# M2.net
KiCad netlist of a schematic drawn in Altium Designer
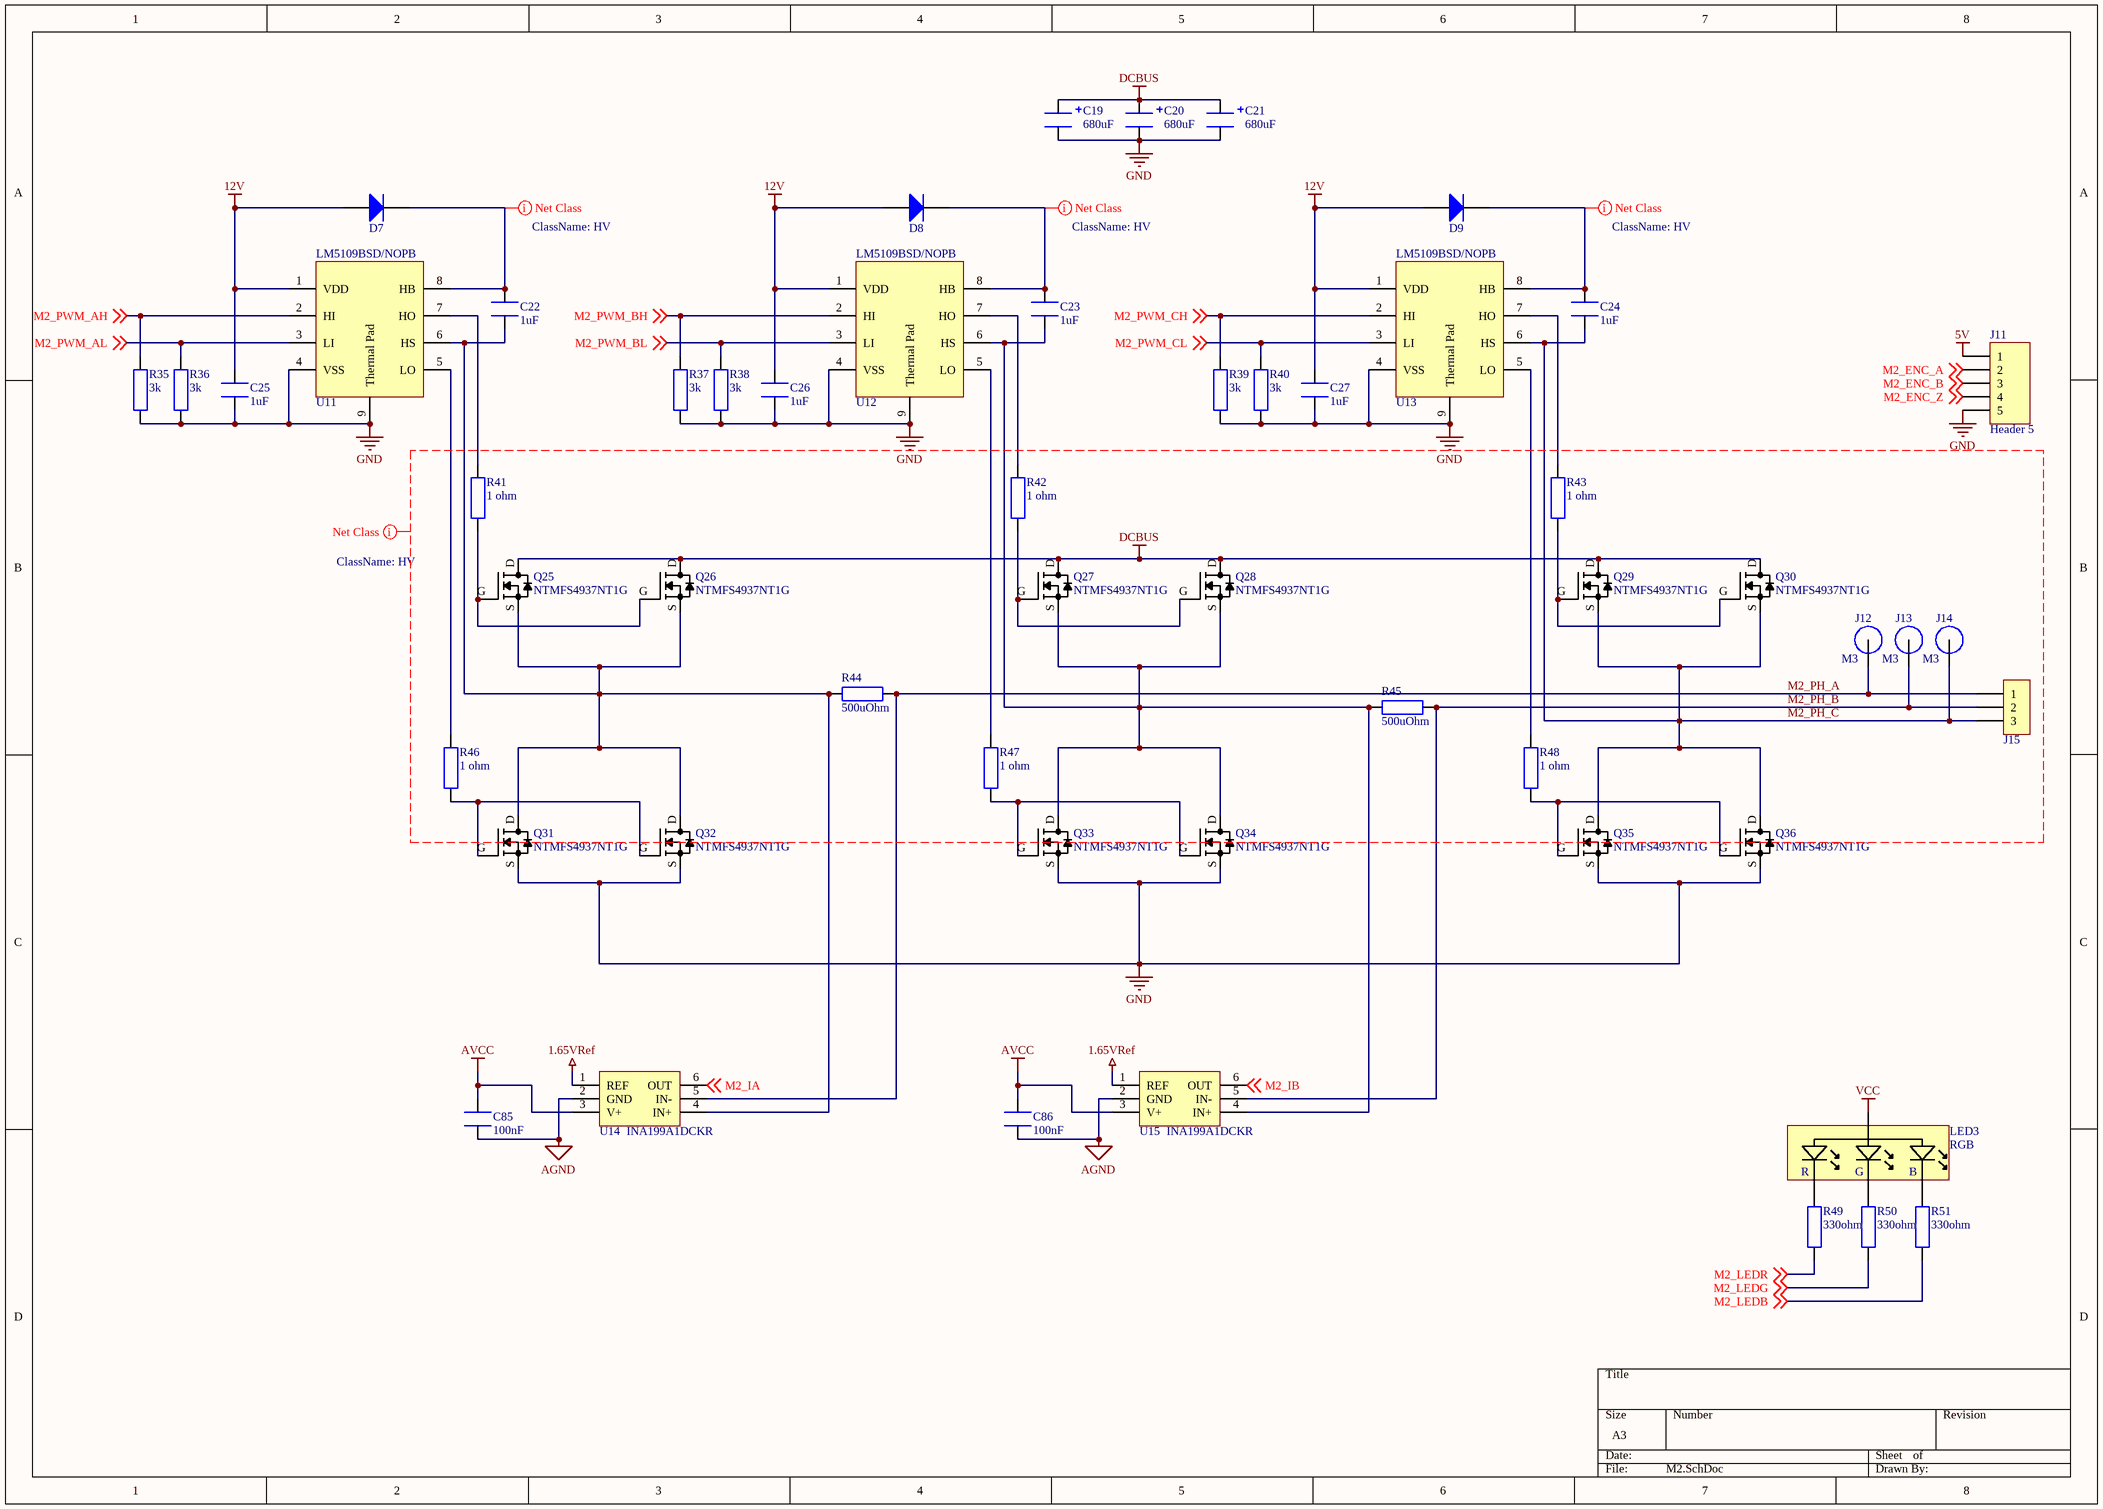
[diagram p0: M2.SchDoc]

(export (version "E")
  (design (tool "Eeschema 10.0.6"))
  (components
    (comp (ref "C19")
      (value "680uF")
      (footprint "CAPE10.0MM_Rad_10x14mm")
      (description "CAP, ALU ELEC, 680UF, 35V, RAD")
      (fields (field (name "Comment") "35ZLH680MEFC10X23"))
      (libsource (lib "CustomComponents") (part "35ZLH680MEFC10X23"))
    )
    (comp (ref "C20")
      (value "680uF")
      (footprint "CAPE10.0MM_Rad_10x14mm")
      (description "CAP, ALU ELEC, 680UF, 35V, RAD")
      (fields (field (name "Comment") "35ZLH680MEFC10X23"))
      (libsource (lib "CustomComponents") (part "35ZLH680MEFC10X23"))
    )
    (comp (ref "C21")
      (value "680uF")
      (footprint "CAPE10.0MM_Rad_10x14mm")
      (description "CAP, ALU ELEC, 680UF, 35V, RAD")
      (fields (field (name "Comment") "35ZLH680MEFC10X23"))
      (libsource (lib "CustomComponents") (part "35ZLH680MEFC10X23"))
    )
    (comp (ref "C22")
      (value "1uF")
      (footprint "1608[0603]")
      (description "CAP, MLCC, X5R, 1UF, 16V, 0603")
      (fields (field (name "Comment") "MC0603X105K160"))
      (libsource (lib "CustomComponents") (part "MC0603X105K160"))
    )
    (comp (ref "C23")
      (value "1uF")
      (footprint "1608[0603]")
      (description "CAP, MLCC, X5R, 1UF, 16V, 0603")
      (fields (field (name "Comment") "MC0603X105K160"))
      (libsource (lib "CustomComponents") (part "MC0603X105K160"))
    )
    (comp (ref "C24")
      (value "1uF")
      (footprint "1608[0603]")
      (description "CAP, MLCC, X5R, 1UF, 16V, 0603")
      (fields (field (name "Comment") "MC0603X105K160"))
      (libsource (lib "CustomComponents") (part "MC0603X105K160"))
    )
    (comp (ref "C25")
      (value "1uF")
      (footprint "1608[0603]")
      (description "CAP, MLCC, X5R, 1UF, 16V, 0603")
      (fields (field (name "Comment") "MC0603X105K160"))
      (libsource (lib "CustomComponents") (part "MC0603X105K160"))
    )
    (comp (ref "C26")
      (value "1uF")
      (footprint "1608[0603]")
      (description "CAP, MLCC, X5R, 1UF, 16V, 0603")
      (fields (field (name "Comment") "MC0603X105K160"))
      (libsource (lib "CustomComponents") (part "MC0603X105K160"))
    )
    (comp (ref "C27")
      (value "1uF")
      (footprint "1608[0603]")
      (description "CAP, MLCC, X5R, 1UF, 16V, 0603")
      (fields (field (name "Comment") "MC0603X105K160"))
      (libsource (lib "CustomComponents") (part "MC0603X105K160"))
    )
    (comp (ref "C85")
      (value "100nF")
      (footprint "1608[0603]")
      (description "CAP, MLCC, X7R, 100NF, 16V, 0603")
      (fields (field (name "Comment") "MC0603B104K160CT"))
      (libsource (lib "CustomComponents") (part "MC0603B104K160CT"))
    )
    (comp (ref "C86")
      (value "100nF")
      (footprint "1608[0603]")
      (description "CAP, MLCC, X7R, 100NF, 16V, 0603")
      (fields (field (name "Comment") "MC0603B104K160CT"))
      (libsource (lib "CustomComponents") (part "MC0603B104K160CT"))
    )
    (comp (ref "D7")
      (value "RB521S30T1G")
      (footprint "SOD523F")
      (description "DIODE, SCHOTTKY, 200MA, 30V")
      (libsource (lib "CustomComponents") (part "RB521S30T1G"))
    )
    (comp (ref "D8")
      (value "RB521S30T1G")
      (footprint "SOD523F")
      (description "DIODE, SCHOTTKY, 200MA, 30V")
      (libsource (lib "CustomComponents") (part "RB521S30T1G"))
    )
    (comp (ref "D9")
      (value "RB521S30T1G")
      (footprint "SOD523F")
      (description "DIODE, SCHOTTKY, 200MA, 30V")
      (libsource (lib "CustomComponents") (part "RB521S30T1G"))
    )
    (comp (ref "J11")
      (value "Header 5")
      (footprint "HDR1X5")
      (description "Header, 5-Pin")
      (fields (field (name "PUBLISHER") "Altium Limited"))
      (libsource (lib "Miscellaneous Connectors") (part "Header 5"))
    )
    (comp (ref "J12")
      (value "M3")
      (footprint "M3 Spade Hole")
      (description "M3 Spade Terminal")
      (libsource (lib "CustomComponents") (part "M3 Spade Terminal"))
    )
    (comp (ref "J13")
      (value "M3")
      (footprint "M3 Spade Hole")
      (description "M3 Spade Terminal")
      (libsource (lib "CustomComponents") (part "M3 Spade Terminal"))
    )
    (comp (ref "J14")
      (value "M3")
      (footprint "M3 Spade Hole")
      (description "M3 Spade Terminal")
      (libsource (lib "CustomComponents") (part "M3 Spade Terminal"))
    )
    (comp (ref "J15")
      (value "MC000051")
      (footprint "MC000051")
      (description "TERMINAL BLOCK, WIRE TO BRD, 3POS, 10AWG")
      (libsource (lib "CustomComponents") (part "MC000051"))
    )
    (comp (ref "LED3")
      (value "RGB")
      (footprint "ASMB-MTB1")
      (description "LED, HB, RGB, 0.09W, PLCC-4")
      (libsource (lib "CustomComponents") (part "ASMB-MTB1-0A3A2"))
    )
    (comp (ref "Q25")
      (value "NTMFS4937NT1G")
      (footprint "SO8FL")
      (description "MOSFET, N CH, 30V, 70A, SO-8 FL")
      (libsource (lib "CustomComponents") (part "NTMFS4937NT1G"))
    )
    (comp (ref "Q26")
      (value "NTMFS4937NT1G")
      (footprint "SO8FL")
      (description "MOSFET, N CH, 30V, 70A, SO-8 FL")
      (libsource (lib "CustomComponents") (part "NTMFS4937NT1G"))
    )
    (comp (ref "Q27")
      (value "NTMFS4937NT1G")
      (footprint "SO8FL")
      (description "MOSFET, N CH, 30V, 70A, SO-8 FL")
      (libsource (lib "CustomComponents") (part "NTMFS4937NT1G"))
    )
    (comp (ref "Q28")
      (value "NTMFS4937NT1G")
      (footprint "SO8FL")
      (description "MOSFET, N CH, 30V, 70A, SO-8 FL")
      (libsource (lib "CustomComponents") (part "NTMFS4937NT1G"))
    )
    (comp (ref "Q29")
      (value "NTMFS4937NT1G")
      (footprint "SO8FL")
      (description "MOSFET, N CH, 30V, 70A, SO-8 FL")
      (libsource (lib "CustomComponents") (part "NTMFS4937NT1G"))
    )
    (comp (ref "Q30")
      (value "NTMFS4937NT1G")
      (footprint "SO8FL")
      (description "MOSFET, N CH, 30V, 70A, SO-8 FL")
      (libsource (lib "CustomComponents") (part "NTMFS4937NT1G"))
    )
    (comp (ref "Q31")
      (value "NTMFS4937NT1G")
      (footprint "SO8FL")
      (description "MOSFET, N CH, 30V, 70A, SO-8 FL")
      (libsource (lib "CustomComponents") (part "NTMFS4937NT1G"))
    )
    (comp (ref "Q32")
      (value "NTMFS4937NT1G")
      (footprint "SO8FL")
      (description "MOSFET, N CH, 30V, 70A, SO-8 FL")
      (libsource (lib "CustomComponents") (part "NTMFS4937NT1G"))
    )
    (comp (ref "Q33")
      (value "NTMFS4937NT1G")
      (footprint "SO8FL")
      (description "MOSFET, N CH, 30V, 70A, SO-8 FL")
      (libsource (lib "CustomComponents") (part "NTMFS4937NT1G"))
    )
    (comp (ref "Q34")
      (value "NTMFS4937NT1G")
      (footprint "SO8FL")
      (description "MOSFET, N CH, 30V, 70A, SO-8 FL")
      (libsource (lib "CustomComponents") (part "NTMFS4937NT1G"))
    )
    (comp (ref "Q35")
      (value "NTMFS4937NT1G")
      (footprint "SO8FL")
      (description "MOSFET, N CH, 30V, 70A, SO-8 FL")
      (libsource (lib "CustomComponents") (part "NTMFS4937NT1G"))
    )
    (comp (ref "Q36")
      (value "NTMFS4937NT1G")
      (footprint "SO8FL")
      (description "MOSFET, N CH, 30V, 70A, SO-8 FL")
      (libsource (lib "CustomComponents") (part "NTMFS4937NT1G"))
    )
    (comp (ref "R35")
      (value "3k")
      (footprint "RESC1608X55N")
      (description "RESISTOR, 0603, 3K, 1%, ANTI SULFUR")
      (fields (field (name "Comment") "MCMR06X3001FTL"))
      (libsource (lib "CustomComponents") (part "MCMR06X3001FTL"))
    )
    (comp (ref "R36")
      (value "3k")
      (footprint "RESC1608X55N")
      (description "RESISTOR, 0603, 3K, 1%, ANTI SULFUR")
      (fields (field (name "Comment") "MCMR06X3001FTL"))
      (libsource (lib "CustomComponents") (part "MCMR06X3001FTL"))
    )
    (comp (ref "R37")
      (value "3k")
      (footprint "RESC1608X55N")
      (description "RESISTOR, 0603, 3K, 1%, ANTI SULFUR")
      (fields (field (name "Comment") "MCMR06X3001FTL"))
      (libsource (lib "CustomComponents") (part "MCMR06X3001FTL"))
    )
    (comp (ref "R38")
      (value "3k")
      (footprint "RESC1608X55N")
      (description "RESISTOR, 0603, 3K, 1%, ANTI SULFUR")
      (fields (field (name "Comment") "MCMR06X3001FTL"))
      (libsource (lib "CustomComponents") (part "MCMR06X3001FTL"))
    )
    (comp (ref "R39")
      (value "3k")
      (footprint "RESC1608X55N")
      (description "RESISTOR, 0603, 3K, 1%, ANTI SULFUR")
      (fields (field (name "Comment") "MCMR06X3001FTL"))
      (libsource (lib "CustomComponents") (part "MCMR06X3001FTL"))
    )
    (comp (ref "R40")
      (value "3k")
      (footprint "RESC1608X55N")
      (description "RESISTOR, 0603, 3K, 1%, ANTI SULFUR")
      (fields (field (name "Comment") "MCMR06X3001FTL"))
      (libsource (lib "CustomComponents") (part "MCMR06X3001FTL"))
    )
    (comp (ref "R41")
      (value "1 ohm")
      (footprint "RESC1608X55N")
      (description "RES, THICK FILM, 1OHM, 1%, 0.1W")
      (fields (field (name "Comment") "MCWR06W1R00FTL"))
      (libsource (lib "CustomComponents") (part "MCWR06W1R00FTL"))
    )
    (comp (ref "R42")
      (value "1 ohm")
      (footprint "RESC1608X55N")
      (description "RES, THICK FILM, 1OHM, 1%, 0.1W")
      (fields (field (name "Comment") "MCWR06W1R00FTL"))
      (libsource (lib "CustomComponents") (part "MCWR06W1R00FTL"))
    )
    (comp (ref "R43")
      (value "1 ohm")
      (footprint "RESC1608X55N")
      (description "RES, THICK FILM, 1OHM, 1%, 0.1W")
      (fields (field (name "Comment") "MCWR06W1R00FTL"))
      (libsource (lib "CustomComponents") (part "MCWR06W1R00FTL"))
    )
    (comp (ref "R44")
      (value "500uOhm")
      (footprint "RESC6332X70N")
      (description "RESISTOR, R0005, 2.0W, 1%")
      (fields (field (name "Comment") "TLR3A20DR0005FTDG"))
      (libsource (lib "CustomComponents") (part "TLR3A20DR0005FTDG"))
    )
    (comp (ref "R45")
      (value "500uOhm")
      (footprint "RESC6332X70N")
      (description "RESISTOR, R0005, 2.0W, 1%")
      (fields (field (name "Comment") "TLR3A20DR0005FTDG"))
      (libsource (lib "CustomComponents") (part "TLR3A20DR0005FTDG"))
    )
    (comp (ref "R46")
      (value "1 ohm")
      (footprint "RESC1608X55N")
      (description "RES, THICK FILM, 1OHM, 1%, 0.1W")
      (fields (field (name "Comment") "MCWR06W1R00FTL"))
      (libsource (lib "CustomComponents") (part "MCWR06W1R00FTL"))
    )
    (comp (ref "R47")
      (value "1 ohm")
      (footprint "RESC1608X55N")
      (description "RES, THICK FILM, 1OHM, 1%, 0.1W")
      (fields (field (name "Comment") "MCWR06W1R00FTL"))
      (libsource (lib "CustomComponents") (part "MCWR06W1R00FTL"))
    )
    (comp (ref "R48")
      (value "1 ohm")
      (footprint "RESC1608X55N")
      (description "RES, THICK FILM, 1OHM, 1%, 0.1W")
      (fields (field (name "Comment") "MCWR06W1R00FTL"))
      (libsource (lib "CustomComponents") (part "MCWR06W1R00FTL"))
    )
    (comp (ref "R49")
      (value "330ohm")
      (footprint "RESC1608X55N")
      (description "RES, THICK FILM, 330 OHM, 1%, 0.1W")
      (fields (field (name "Comment") "MCWR06X3300FTL"))
      (libsource (lib "CustomComponents") (part "MCWR06X3300FTL"))
    )
    (comp (ref "R50")
      (value "330ohm")
      (footprint "RESC1608X55N")
      (description "RES, THICK FILM, 330 OHM, 1%, 0.1W")
      (fields (field (name "Comment") "MCWR06X3300FTL"))
      (libsource (lib "CustomComponents") (part "MCWR06X3300FTL"))
    )
    (comp (ref "R51")
      (value "330ohm")
      (footprint "RESC1608X55N")
      (description "RES, THICK FILM, 330 OHM, 1%, 0.1W")
      (fields (field (name "Comment") "MCWR06X3300FTL"))
      (libsource (lib "CustomComponents") (part "MCWR06X3300FTL"))
    )
    (comp (ref "U11")
      (value "LM5109BSD/NOPB")
      (footprint "SON80P400X80_HS-9N")
      (description "DRIVER, MOSFET, HALF BRIDGE, WSON-8, 1A")
      (libsource (lib "CustomComponents") (part "LM5109BSD/NOPB"))
    )
    (comp (ref "U12")
      (value "LM5109BSD/NOPB")
      (footprint "SON80P400X80_HS-9N")
      (description "DRIVER, MOSFET, HALF BRIDGE, WSON-8, 1A")
      (libsource (lib "CustomComponents") (part "LM5109BSD/NOPB"))
    )
    (comp (ref "U13")
      (value "LM5109BSD/NOPB")
      (footprint "SON80P400X80_HS-9N")
      (description "DRIVER, MOSFET, HALF BRIDGE, WSON-8, 1A")
      (libsource (lib "CustomComponents") (part "LM5109BSD/NOPB"))
    )
    (comp (ref "U14")
      (value "INA199A1DCKR")
      (footprint "TSOP65P210X110-6N")
      (description "CURRENT SENSE AMP, 50V/V, 80KHZ")
      (libsource (lib "CustomComponents") (part "INA199A1DCKR"))
    )
    (comp (ref "U15")
      (value "INA199A1DCKR")
      (footprint "TSOP65P210X110-6N")
      (description "CURRENT SENSE AMP, 50V/V, 80KHZ")
      (libsource (lib "CustomComponents") (part "INA199A1DCKR"))
    )
  )
  (nets
    (net (code "1") (name "/M2_PH_A") (class "Default")
      (node (ref "J12") (pin "1") (pinfunction "1_1") (pintype "passive"))
      (node (ref "J15") (pin "1") (pinfunction "1_1") (pintype "passive"))
      (node (ref "R44") (pin "1") (pinfunction "0_1") (pintype "passive"))
      (node (ref "U14") (pin "5") (pinfunction "IN-_5") (pintype "passive"))
    )
    (net (code "2") (name "/M2_PH_B") (class "Default")
      (node (ref "J13") (pin "1") (pinfunction "1_1") (pintype "passive"))
      (node (ref "J15") (pin "2") (pinfunction "2_2") (pintype "passive"))
      (node (ref "R45") (pin "1") (pinfunction "0_1") (pintype "passive"))
      (node (ref "U15") (pin "5") (pinfunction "IN-_5") (pintype "passive"))
    )
    (net (code "3") (name "/M2_PH_C") (class "Default")
      (node (ref "C24") (pin "1") (pinfunction "1_1") (pintype "passive"))
      (node (ref "J14") (pin "1") (pinfunction "1_1") (pintype "passive"))
      (node (ref "J15") (pin "3") (pinfunction "3_3") (pintype "passive"))
      (node (ref "Q29") (pin "S") (pinfunction "S_S") (pintype "passive"))
      (node (ref "Q30") (pin "S") (pinfunction "S_S") (pintype "passive"))
      (node (ref "Q35") (pin "D") (pinfunction "D_D") (pintype "passive"))
      (node (ref "Q36") (pin "D") (pinfunction "D_D") (pintype "passive"))
      (node (ref "U13") (pin "6") (pinfunction "HS_6") (pintype "passive"))
    )
    (net (code "4") (name "1.65VRef") (class "Default")
      (node (ref "U14") (pin "1") (pinfunction "REF_1") (pintype "passive"))
      (node (ref "U15") (pin "1") (pinfunction "REF_1") (pintype "passive"))
    )
    (net (code "5") (name "5V") (class "Default")
      (node (ref "J11") (pin "1") (pinfunction "1_1") (pintype "passive"))
    )
    (net (code "6") (name "12V") (class "Default")
      (node (ref "C25") (pin "2") (pinfunction "2_2") (pintype "passive"))
      (node (ref "C26") (pin "2") (pinfunction "2_2") (pintype "passive"))
      (node (ref "C27") (pin "2") (pinfunction "2_2") (pintype "passive"))
      (node (ref "D7") (pin "A") (pinfunction "A_A") (pintype "passive"))
      (node (ref "D8") (pin "A") (pinfunction "A_A") (pintype "passive"))
      (node (ref "D9") (pin "A") (pinfunction "A_A") (pintype "passive"))
      (node (ref "U11") (pin "1") (pinfunction "VDD_1") (pintype "passive"))
      (node (ref "U12") (pin "1") (pinfunction "VDD_1") (pintype "passive"))
      (node (ref "U13") (pin "1") (pinfunction "VDD_1") (pintype "passive"))
    )
    (net (code "7") (name "AGND") (class "Default")
      (node (ref "C85") (pin "1") (pinfunction "1_1") (pintype "passive"))
      (node (ref "C86") (pin "1") (pinfunction "1_1") (pintype "passive"))
      (node (ref "U14") (pin "2") (pinfunction "GND_2") (pintype "passive"))
      (node (ref "U15") (pin "2") (pinfunction "GND_2") (pintype "passive"))
    )
    (net (code "8") (name "AVCC") (class "Default")
      (node (ref "C85") (pin "2") (pinfunction "2_2") (pintype "passive"))
      (node (ref "C86") (pin "2") (pinfunction "2_2") (pintype "passive"))
      (node (ref "U14") (pin "3") (pinfunction "V+_3") (pintype "passive"))
      (node (ref "U15") (pin "3") (pinfunction "V+_3") (pintype "passive"))
    )
    (net (code "9") (name "DCBUS") (class "Default")
      (node (ref "C19") (pin "1") (pinfunction "1_1") (pintype "passive"))
      (node (ref "C20") (pin "1") (pinfunction "1_1") (pintype "passive"))
      (node (ref "C21") (pin "1") (pinfunction "1_1") (pintype "passive"))
      (node (ref "Q25") (pin "D") (pinfunction "D_D") (pintype "passive"))
      (node (ref "Q26") (pin "D") (pinfunction "D_D") (pintype "passive"))
      (node (ref "Q27") (pin "D") (pinfunction "D_D") (pintype "passive"))
      (node (ref "Q28") (pin "D") (pinfunction "D_D") (pintype "passive"))
      (node (ref "Q29") (pin "D") (pinfunction "D_D") (pintype "passive"))
      (node (ref "Q30") (pin "D") (pinfunction "D_D") (pintype "passive"))
    )
    (net (code "10") (name "GND") (class "Default")
      (node (ref "C19") (pin "2") (pinfunction "2_2") (pintype "passive"))
      (node (ref "C20") (pin "2") (pinfunction "2_2") (pintype "passive"))
      (node (ref "C21") (pin "2") (pinfunction "2_2") (pintype "passive"))
      (node (ref "C25") (pin "1") (pinfunction "1_1") (pintype "passive"))
      (node (ref "C26") (pin "1") (pinfunction "1_1") (pintype "passive"))
      (node (ref "C27") (pin "1") (pinfunction "1_1") (pintype "passive"))
      (node (ref "J11") (pin "5") (pinfunction "5_5") (pintype "passive"))
      (node (ref "Q31") (pin "S") (pinfunction "S_S") (pintype "passive"))
      (node (ref "Q32") (pin "S") (pinfunction "S_S") (pintype "passive"))
      (node (ref "Q33") (pin "S") (pinfunction "S_S") (pintype "passive"))
      (node (ref "Q34") (pin "S") (pinfunction "S_S") (pintype "passive"))
      (node (ref "Q35") (pin "S") (pinfunction "S_S") (pintype "passive"))
      (node (ref "Q36") (pin "S") (pinfunction "S_S") (pintype "passive"))
      (node (ref "R35") (pin "1") (pinfunction "0_1") (pintype "passive"))
      (node (ref "R36") (pin "1") (pinfunction "0_1") (pintype "passive"))
      (node (ref "R37") (pin "1") (pinfunction "0_1") (pintype "passive"))
      (node (ref "R38") (pin "1") (pinfunction "0_1") (pintype "passive"))
      (node (ref "R39") (pin "1") (pinfunction "0_1") (pintype "passive"))
      (node (ref "R40") (pin "1") (pinfunction "0_1") (pintype "passive"))
      (node (ref "U11") (pin "4") (pinfunction "VSS_4") (pintype "passive"))
      (node (ref "U11") (pin "9") (pinfunction "Thermal_Pad_9") (pintype "passive"))
      (node (ref "U12") (pin "4") (pinfunction "VSS_4") (pintype "passive"))
      (node (ref "U12") (pin "9") (pinfunction "Thermal_Pad_9") (pintype "passive"))
      (node (ref "U13") (pin "4") (pinfunction "VSS_4") (pintype "passive"))
      (node (ref "U13") (pin "9") (pinfunction "Thermal_Pad_9") (pintype "passive"))
    )
    (net (code "11") (name "M2_ENC_A") (class "Default")
      (node (ref "J11") (pin "2") (pinfunction "2_2") (pintype "passive"))
    )
    (net (code "12") (name "M2_ENC_B") (class "Default")
      (node (ref "J11") (pin "3") (pinfunction "3_3") (pintype "passive"))
    )
    (net (code "13") (name "M2_ENC_Z") (class "Default")
      (node (ref "J11") (pin "4") (pinfunction "4_4") (pintype "passive"))
    )
    (net (code "14") (name "M2_IA") (class "Default")
      (node (ref "U14") (pin "6") (pinfunction "OUT_6") (pintype "passive"))
    )
    (net (code "15") (name "M2_IB") (class "Default")
      (node (ref "U15") (pin "6") (pinfunction "OUT_6") (pintype "passive"))
    )
    (net (code "16") (name "M2_LEDB") (class "Default")
      (node (ref "R51") (pin "2") (pinfunction "0_2") (pintype "passive"))
    )
    (net (code "17") (name "M2_LEDG") (class "Default")
      (node (ref "R50") (pin "2") (pinfunction "0_2") (pintype "passive"))
    )
    (net (code "18") (name "M2_LEDR") (class "Default")
      (node (ref "R49") (pin "2") (pinfunction "0_2") (pintype "passive"))
    )
    (net (code "19") (name "M2_PWM_AH") (class "Default")
      (node (ref "R35") (pin "2") (pinfunction "0_2") (pintype "passive"))
      (node (ref "U11") (pin "2") (pinfunction "HI_2") (pintype "passive"))
    )
    (net (code "20") (name "M2_PWM_AL") (class "Default")
      (node (ref "R36") (pin "2") (pinfunction "0_2") (pintype "passive"))
      (node (ref "U11") (pin "3") (pinfunction "LI_3") (pintype "passive"))
    )
    (net (code "21") (name "M2_PWM_BH") (class "Default")
      (node (ref "R37") (pin "2") (pinfunction "0_2") (pintype "passive"))
      (node (ref "U12") (pin "2") (pinfunction "HI_2") (pintype "passive"))
    )
    (net (code "22") (name "M2_PWM_BL") (class "Default")
      (node (ref "R38") (pin "2") (pinfunction "0_2") (pintype "passive"))
      (node (ref "U12") (pin "3") (pinfunction "LI_3") (pintype "passive"))
    )
    (net (code "23") (name "M2_PWM_CH") (class "Default")
      (node (ref "R39") (pin "2") (pinfunction "0_2") (pintype "passive"))
      (node (ref "U13") (pin "2") (pinfunction "HI_2") (pintype "passive"))
    )
    (net (code "24") (name "M2_PWM_CL") (class "Default")
      (node (ref "R40") (pin "2") (pinfunction "0_2") (pintype "passive"))
      (node (ref "U13") (pin "3") (pinfunction "LI_3") (pintype "passive"))
    )
    (net (code "25") (name "Net-(LED3-B)") (class "Default")
      (node (ref "LED3") (pin "3") (pinfunction "B_3") (pintype "passive"))
      (node (ref "R51") (pin "1") (pinfunction "0_1") (pintype "passive"))
    )
    (net (code "26") (name "Net-(LED3-G)") (class "Default")
      (node (ref "LED3") (pin "2") (pinfunction "G_2") (pintype "passive"))
      (node (ref "R50") (pin "1") (pinfunction "0_1") (pintype "passive"))
    )
    (net (code "27") (name "Net-(LED3-R)") (class "Default")
      (node (ref "LED3") (pin "1") (pinfunction "R_1") (pintype "passive"))
      (node (ref "R49") (pin "1") (pinfunction "0_1") (pintype "passive"))
    )
    (net (code "28") (name "Net-(Q25-PadG)") (class "Default")
      (node (ref "Q25") (pin "G") (pinfunction "G_G") (pintype "passive"))
      (node (ref "Q26") (pin "G") (pinfunction "G_G") (pintype "passive"))
      (node (ref "R41") (pin "1") (pinfunction "0_1") (pintype "passive"))
    )
    (net (code "29") (name "Net-(Q27-PadG)") (class "Default")
      (node (ref "Q27") (pin "G") (pinfunction "G_G") (pintype "passive"))
      (node (ref "Q28") (pin "G") (pinfunction "G_G") (pintype "passive"))
      (node (ref "R42") (pin "1") (pinfunction "0_1") (pintype "passive"))
    )
    (net (code "30") (name "Net-(Q29-PadG)") (class "Default")
      (node (ref "Q29") (pin "G") (pinfunction "G_G") (pintype "passive"))
      (node (ref "Q30") (pin "G") (pinfunction "G_G") (pintype "passive"))
      (node (ref "R43") (pin "1") (pinfunction "0_1") (pintype "passive"))
    )
    (net (code "31") (name "Net-(Q31-PadG)") (class "Default")
      (node (ref "Q31") (pin "G") (pinfunction "G_G") (pintype "passive"))
      (node (ref "Q32") (pin "G") (pinfunction "G_G") (pintype "passive"))
      (node (ref "R46") (pin "1") (pinfunction "0_1") (pintype "passive"))
    )
    (net (code "32") (name "Net-(Q33-PadG)") (class "Default")
      (node (ref "Q33") (pin "G") (pinfunction "G_G") (pintype "passive"))
      (node (ref "Q34") (pin "G") (pinfunction "G_G") (pintype "passive"))
      (node (ref "R47") (pin "1") (pinfunction "0_1") (pintype "passive"))
    )
    (net (code "33") (name "Net-(Q35-PadG)") (class "Default")
      (node (ref "Q35") (pin "G") (pinfunction "G_G") (pintype "passive"))
      (node (ref "Q36") (pin "G") (pinfunction "G_G") (pintype "passive"))
      (node (ref "R48") (pin "1") (pinfunction "0_1") (pintype "passive"))
    )
    (net (code "34") (name "Net-(U11-HB)") (class "Default")
      (node (ref "C22") (pin "2") (pinfunction "2_2") (pintype "passive"))
      (node (ref "D7") (pin "K") (pinfunction "K_K") (pintype "passive"))
      (node (ref "U11") (pin "8") (pinfunction "HB_8") (pintype "passive"))
    )
    (net (code "35") (name "Net-(U11-HO)") (class "Default")
      (node (ref "R41") (pin "2") (pinfunction "0_2") (pintype "passive"))
      (node (ref "U11") (pin "7") (pinfunction "HO_7") (pintype "passive"))
    )
    (net (code "36") (name "Net-(U11-HS)") (class "Default")
      (node (ref "C22") (pin "1") (pinfunction "1_1") (pintype "passive"))
      (node (ref "Q25") (pin "S") (pinfunction "S_S") (pintype "passive"))
      (node (ref "Q26") (pin "S") (pinfunction "S_S") (pintype "passive"))
      (node (ref "Q31") (pin "D") (pinfunction "D_D") (pintype "passive"))
      (node (ref "Q32") (pin "D") (pinfunction "D_D") (pintype "passive"))
      (node (ref "R44") (pin "2") (pinfunction "0_2") (pintype "passive"))
      (node (ref "U11") (pin "6") (pinfunction "HS_6") (pintype "passive"))
      (node (ref "U14") (pin "4") (pinfunction "IN+_4") (pintype "passive"))
    )
    (net (code "37") (name "Net-(U11-LO)") (class "Default")
      (node (ref "R46") (pin "2") (pinfunction "0_2") (pintype "passive"))
      (node (ref "U11") (pin "5") (pinfunction "LO_5") (pintype "passive"))
    )
    (net (code "38") (name "Net-(U12-HB)") (class "Default")
      (node (ref "C23") (pin "2") (pinfunction "2_2") (pintype "passive"))
      (node (ref "D8") (pin "K") (pinfunction "K_K") (pintype "passive"))
      (node (ref "U12") (pin "8") (pinfunction "HB_8") (pintype "passive"))
    )
    (net (code "39") (name "Net-(U12-HO)") (class "Default")
      (node (ref "R42") (pin "2") (pinfunction "0_2") (pintype "passive"))
      (node (ref "U12") (pin "7") (pinfunction "HO_7") (pintype "passive"))
    )
    (net (code "40") (name "Net-(U12-HS)") (class "Default")
      (node (ref "C23") (pin "1") (pinfunction "1_1") (pintype "passive"))
      (node (ref "Q27") (pin "S") (pinfunction "S_S") (pintype "passive"))
      (node (ref "Q28") (pin "S") (pinfunction "S_S") (pintype "passive"))
      (node (ref "Q33") (pin "D") (pinfunction "D_D") (pintype "passive"))
      (node (ref "Q34") (pin "D") (pinfunction "D_D") (pintype "passive"))
      (node (ref "R45") (pin "2") (pinfunction "0_2") (pintype "passive"))
      (node (ref "U12") (pin "6") (pinfunction "HS_6") (pintype "passive"))
      (node (ref "U15") (pin "4") (pinfunction "IN+_4") (pintype "passive"))
    )
    (net (code "41") (name "Net-(U12-LO)") (class "Default")
      (node (ref "R47") (pin "2") (pinfunction "0_2") (pintype "passive"))
      (node (ref "U12") (pin "5") (pinfunction "LO_5") (pintype "passive"))
    )
    (net (code "42") (name "Net-(U13-HB)") (class "Default")
      (node (ref "C24") (pin "2") (pinfunction "2_2") (pintype "passive"))
      (node (ref "D9") (pin "K") (pinfunction "K_K") (pintype "passive"))
      (node (ref "U13") (pin "8") (pinfunction "HB_8") (pintype "passive"))
    )
    (net (code "43") (name "Net-(U13-HO)") (class "Default")
      (node (ref "R43") (pin "2") (pinfunction "0_2") (pintype "passive"))
      (node (ref "U13") (pin "7") (pinfunction "HO_7") (pintype "passive"))
    )
    (net (code "44") (name "Net-(U13-LO)") (class "Default")
      (node (ref "R48") (pin "2") (pinfunction "0_2") (pintype "passive"))
      (node (ref "U13") (pin "5") (pinfunction "LO_5") (pintype "passive"))
    )
    (net (code "45") (name "VCC") (class "Default")
      (node (ref "LED3") (pin "4") (pinfunction "A_4") (pintype "passive"))
    )
  )
)
